# attinier84-motherboard-mk-3_2.net
KiCad netlist of a schematic drawn in EAGLE
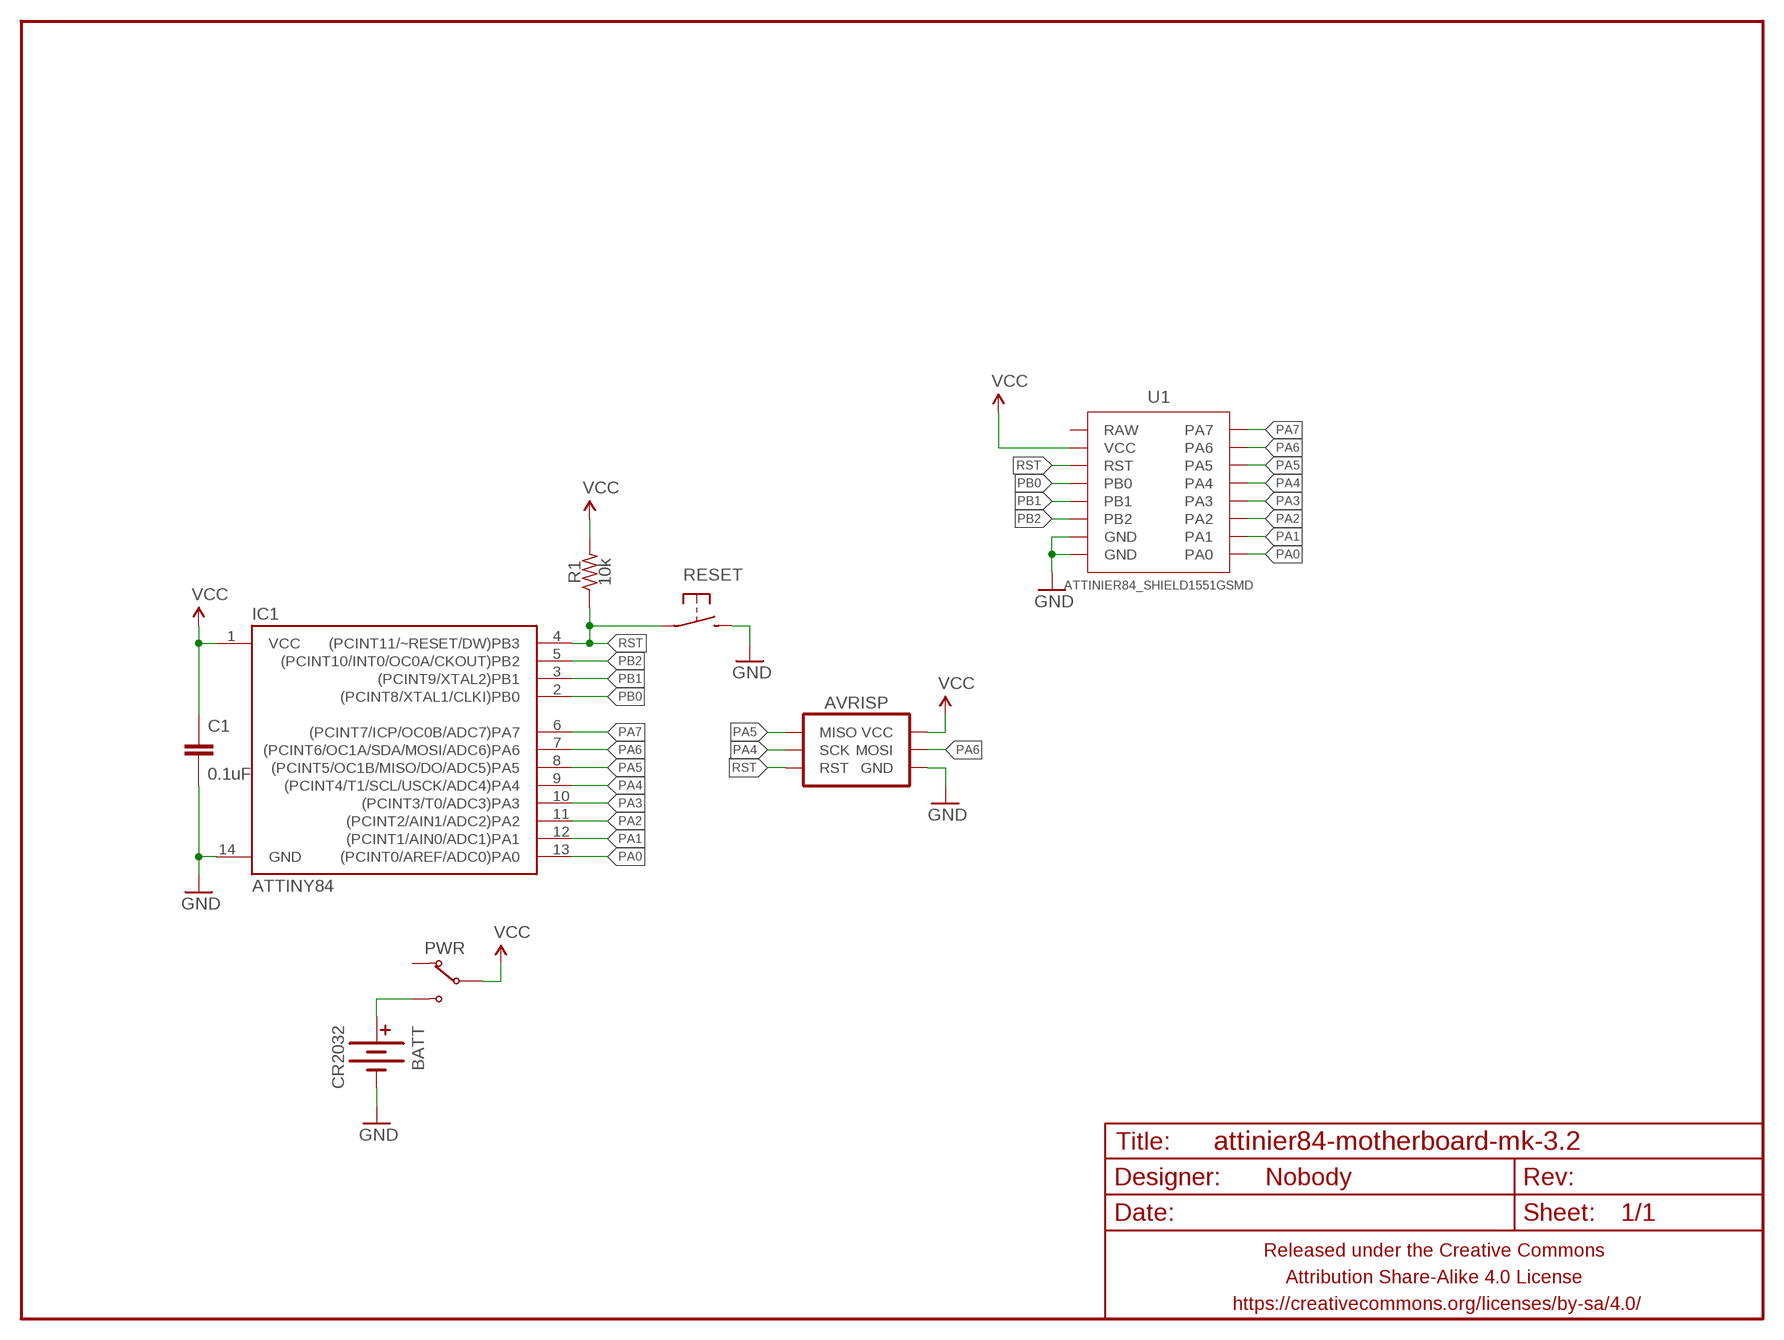
[diagram p0: schematic, sheet 1]

(export (version "E")
  (design (tool "Eeschema 10.0.6"))
  (components
    (comp (ref "AVRISP")
      (value "AVR_SPI_PRG_6PTH")
      (footprint "eagle-import:2X3")
      (libsource (lib "eagle-import") (part "AVR_SPI_PRG_6PTH"))
    )
    (comp (ref "BATT")
      (value "CR2032")
      (footprint "eagle-import:BATTCON_20MM_PTH_TOPLOAD")
      (libsource (lib "eagle-import") (part "BATTERY20PTH_TOPLOAD"))
    )
    (comp (ref "C1")
      (value "0.1uF")
      (footprint "eagle-import:C0805")
      (libsource (lib "eagle-import") (part "CAPACITOR-CERAMICC0805"))
    )
    (comp (ref "FRAME1")
      (value "FRAME-LETTERNO_PACKAGE")
      (footprint "eagle-import:DUMMY")
      (fields (field (name "DESIGNER") "Nobody"))
      (libsource (lib "eagle-import") (part "FRAME-LETTERNO_PACKAGE"))
    )
    (comp (ref "IC1")
      (value "ATTINY84")
      (footprint "eagle-import:SO14")
      (libsource (lib "eagle-import") (part "ATTINY84"))
    )
    (comp (ref "PWR")
      (value "SWITCH-SPDTPTH-RA-2.54MM")
      (footprint "eagle-import:SPDT-RA-2.54MM")
      (libsource (lib "eagle-import") (part "SWITCH-SPDTPTH-RA-2.54MM"))
    )
    (comp (ref "R1")
      (value "10k")
      (footprint "eagle-import:R0805")
      (libsource (lib "eagle-import") (part "RESISTORR0805"))
    )
    (comp (ref "RESET")
      (value "SPST-NO-TACT3MM-RA")
      (footprint "eagle-import:TACTILE-PTH-SIDE")
      (libsource (lib "eagle-import") (part "SPST-NO-TACT3MM-RA"))
    )
    (comp (ref "U1")
      (value "ATTINIER84_SHIELD1551GSMD")
      (footprint "eagle-import:ATTINIER84_SHIELD2_SMD")
      (libsource (lib "eagle-import") (part "ATTINIER84_SHIELD1551GSMD"))
    )
  )
  (nets
    (net (code "1") (name "GND") (class "Default")
      (node (ref "AVRISP") (pin "6") (pinfunction "GND_6") (pintype "passive"))
      (node (ref "BATT") (pin "-") (pinfunction "-_-") (pintype "power_in"))
      (node (ref "C1") (pin "2") (pinfunction "2_2") (pintype "passive"))
      (node (ref "IC1") (pin "14") (pinfunction "GND_14") (pintype "bidirectional"))
      (node (ref "RESET") (pin "2") (pinfunction "2_2") (pintype "passive"))
      (node (ref "U1") (pin "GND@1") (pinfunction "GND_GND@1") (pintype "bidirectional"))
      (node (ref "U1") (pin "GND@2") (pinfunction "GND_GND@2") (pintype "bidirectional"))
    )
    (net (code "2") (name "Net-(PWR-NO)") (class "Default")
      (node (ref "BATT") (pin "+") (pinfunction "+_+") (pintype "power_in"))
      (node (ref "PWR") (pin "3") (pinfunction "NO_3") (pintype "passive"))
    )
    (net (code "3") (name "PA0") (class "Default")
      (node (ref "IC1") (pin "13") (pinfunction "(PCINT0/AREF/ADC0)PA0_13") (pintype "bidirectional"))
      (node (ref "U1") (pin "PA0") (pinfunction "PA0_PA0") (pintype "bidirectional"))
    )
    (net (code "4") (name "PA1") (class "Default")
      (node (ref "IC1") (pin "12") (pinfunction "(PCINT1/AIN0/ADC1)PA1_12") (pintype "bidirectional"))
      (node (ref "U1") (pin "PA1") (pinfunction "PA1_PA1") (pintype "bidirectional"))
    )
    (net (code "5") (name "PA2") (class "Default")
      (node (ref "IC1") (pin "11") (pinfunction "(PCINT2/AIN1/ADC2)PA2_11") (pintype "bidirectional"))
      (node (ref "U1") (pin "PA2") (pinfunction "PA2_PA2") (pintype "bidirectional"))
    )
    (net (code "6") (name "PA3") (class "Default")
      (node (ref "IC1") (pin "10") (pinfunction "(PCINT3/T0/ADC3)PA3_10") (pintype "bidirectional"))
      (node (ref "U1") (pin "PA3") (pinfunction "PA3_PA3") (pintype "bidirectional"))
    )
    (net (code "7") (name "PA4") (class "Default")
      (node (ref "AVRISP") (pin "3") (pinfunction "SCK_3") (pintype "passive"))
      (node (ref "IC1") (pin "9") (pinfunction "(PCINT4/T1/SCL/USCK/ADC4)PA4_9") (pintype "bidirectional"))
      (node (ref "U1") (pin "PA4") (pinfunction "PA4_PA4") (pintype "bidirectional"))
    )
    (net (code "8") (name "PA5") (class "Default")
      (node (ref "AVRISP") (pin "1") (pinfunction "MISO_1") (pintype "passive"))
      (node (ref "IC1") (pin "8") (pinfunction "(PCINT5/OC1B/MISO/DO/ADC5)PA5_8") (pintype "bidirectional"))
      (node (ref "U1") (pin "PA5") (pinfunction "PA5_PA5") (pintype "bidirectional"))
    )
    (net (code "9") (name "PA6") (class "Default")
      (node (ref "AVRISP") (pin "4") (pinfunction "MOSI_4") (pintype "passive"))
      (node (ref "IC1") (pin "7") (pinfunction "(PCINT6/OC1A/SDA/MOSI/ADC6)PA6_7") (pintype "bidirectional"))
      (node (ref "U1") (pin "PA6") (pinfunction "PA6_PA6") (pintype "bidirectional"))
    )
    (net (code "10") (name "PA7") (class "Default")
      (node (ref "IC1") (pin "6") (pinfunction "(PCINT7/ICP/OC0B/ADC7)PA7_6") (pintype "bidirectional"))
      (node (ref "U1") (pin "PA7") (pinfunction "PA7_PA7") (pintype "bidirectional"))
    )
    (net (code "11") (name "PB0") (class "Default")
      (node (ref "IC1") (pin "2") (pinfunction "(PCINT8/XTAL1/CLKI)PB0_2") (pintype "bidirectional"))
      (node (ref "U1") (pin "PB0") (pinfunction "PB0_PB0") (pintype "bidirectional"))
    )
    (net (code "12") (name "PB1") (class "Default")
      (node (ref "IC1") (pin "3") (pinfunction "(PCINT9/XTAL2)PB1_3") (pintype "bidirectional"))
      (node (ref "U1") (pin "PB1") (pinfunction "PB1_PB1") (pintype "bidirectional"))
    )
    (net (code "13") (name "PB2") (class "Default")
      (node (ref "IC1") (pin "5") (pinfunction "(PCINT10/INT0/OC0A/CKOUT)PB2_5") (pintype "bidirectional"))
      (node (ref "U1") (pin "PB2") (pinfunction "PB2_PB2") (pintype "bidirectional"))
    )
    (net (code "14") (name "RST") (class "Default")
      (node (ref "AVRISP") (pin "5") (pinfunction "RST_5") (pintype "passive"))
      (node (ref "IC1") (pin "4") (pinfunction "(PCINT11/~{RESET/DW})PB3_4") (pintype "bidirectional"))
      (node (ref "R1") (pin "1") (pinfunction "1_1") (pintype "passive"))
      (node (ref "RESET") (pin "1") (pinfunction "1_1") (pintype "passive"))
      (node (ref "U1") (pin "RST") (pinfunction "RST_RST") (pintype "bidirectional"))
    )
    (net (code "15") (name "VCC") (class "Default")
      (node (ref "AVRISP") (pin "2") (pinfunction "VCC_2") (pintype "passive"))
      (node (ref "C1") (pin "1") (pinfunction "1_1") (pintype "passive"))
      (node (ref "IC1") (pin "1") (pinfunction "VCC_1") (pintype "bidirectional"))
      (node (ref "PWR") (pin "2") (pinfunction "COM_2") (pintype "passive"))
      (node (ref "R1") (pin "2") (pinfunction "2_2") (pintype "passive"))
      (node (ref "U1") (pin "VCC") (pinfunction "VCC_VCC") (pintype "bidirectional"))
    )
    (net (code "16") (name "unconnected-(PWR-NC-Pad1)") (class "Default")
      (node (ref "PWR") (pin "1") (pinfunction "NC_1") (pintype "passive"))
    )
    (net (code "17") (name "unconnected-(U1-PadRAW)") (class "Default")
      (node (ref "U1") (pin "RAW") (pinfunction "RAW_RAW") (pintype "bidirectional"))
    )
  )
)
